# Ports.net
KiCad netlist of a schematic drawn in Altium Designer
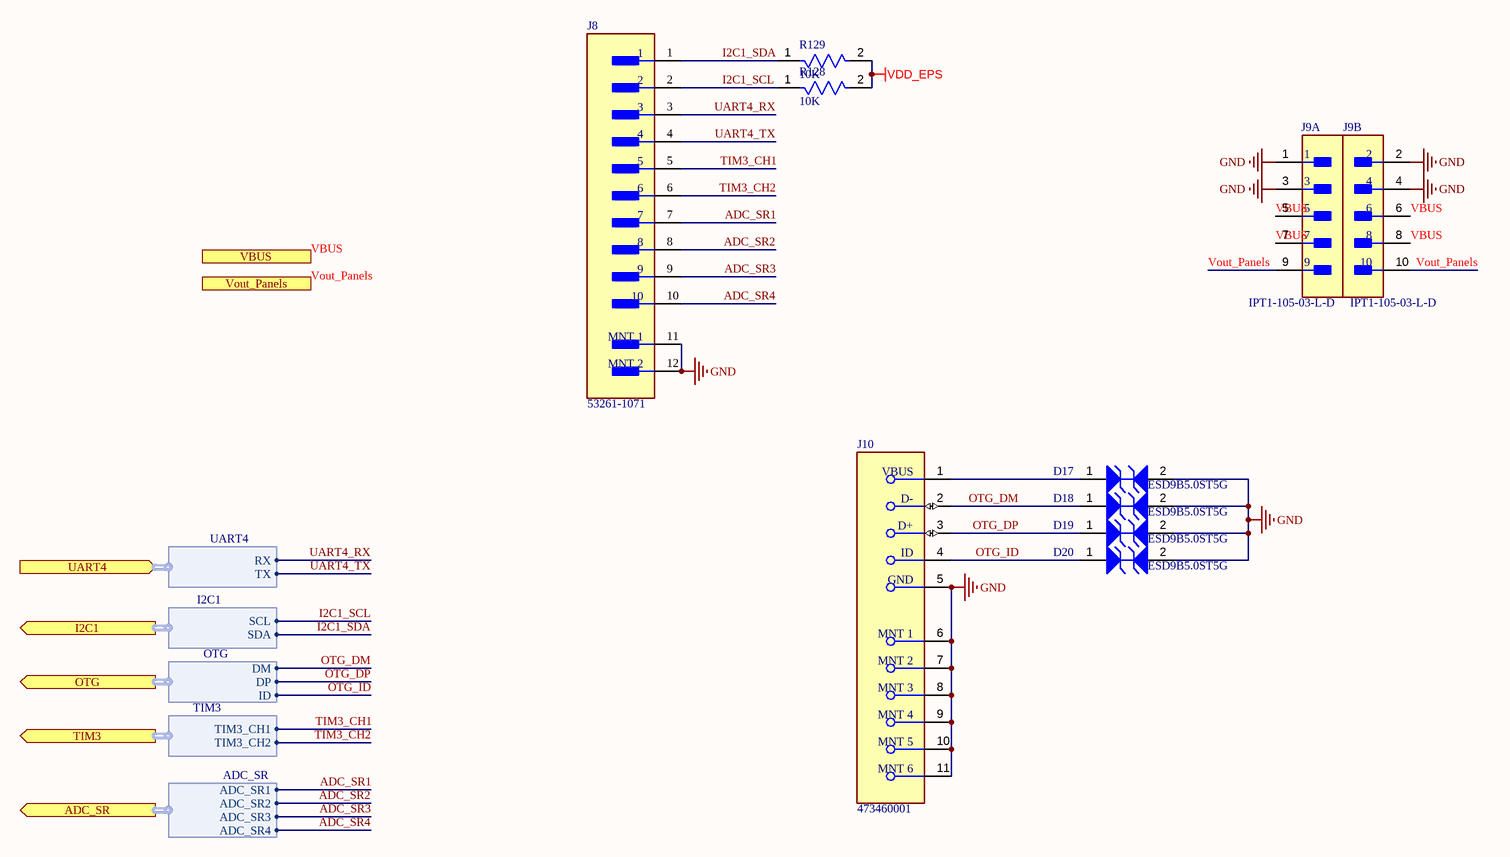
[diagram p0: Ports.SchDoc]

(export (version "E")
  (design (tool "Eeschema 10.0.6"))
  (components
    (comp (ref "D17")
      (value "ESD9B5.0ST5G")
      (footprint "ONSC-SOD-923-2-514AB-01_V")
      (fields (field (name "MANUFACTURER") "On Semiconductor"))
      (libsource (lib "Altium Content Vault") (part "ONSC-A1A2-2"))
    )
    (comp (ref "D18")
      (value "ESD9B5.0ST5G")
      (footprint "ONSC-SOD-923-2-514AB-01_V")
      (fields (field (name "MANUFACTURER") "On Semiconductor"))
      (libsource (lib "Altium Content Vault") (part "ONSC-A1A2-2"))
    )
    (comp (ref "D19")
      (value "ESD9B5.0ST5G")
      (footprint "ONSC-SOD-923-2-514AB-01_V")
      (fields (field (name "MANUFACTURER") "On Semiconductor"))
      (libsource (lib "Altium Content Vault") (part "ONSC-A1A2-2"))
    )
    (comp (ref "D20")
      (value "ESD9B5.0ST5G")
      (footprint "ONSC-SOD-923-2-514AB-01_V")
      (fields (field (name "MANUFACTURER") "On Semiconductor"))
      (libsource (lib "Altium Content Vault") (part "ONSC-A1A2-2"))
    )
    (comp (ref "J8")
      (value "53261-1071")
      (footprint "FP-532611071-MFG")
      (libsource (lib "Altium Content Vault") (part "6fa52caac0d1ee56d9e6a1d806c5b84"))
    )
    (comp (ref "J9")
      (value "IPT1-105-03-L-D")
      (footprint "FP-IPT1-105-03-L-D-MFG")
      (description "CONN HEADER VERT 10POS 2.54MM")
      (fields
        (field (name "MANUFACTURER") "Samtec")
        (field (name "OCTOPART") "https://octopart.com/ipt1-105-03-l-d-samtec-19544968")
      )
      (libsource (lib "") (part "544f42128f4185dcb88ce1ce9bf1982_1"))
    )
    (comp (ref "J10")
      (value "473460001")
      (footprint "FP-473460001-MFG")
      (description "CONN RCPT USB2.0 MICRO B SMD R/A")
      (fields
        (field (name "OCTOPART") "https://octopart.com/47346-0001-molex-7164928")
        (field (name "MANUFACTURER") "Molex")
      )
      (libsource (lib "Altium Content Vault") (part "53ae1f1d9b557310b43ca686e5bb76a"))
    )
    (comp (ref "R128")
      (value "10K")
      (footprint "FP-RK73B1J-MFG")
      (description "RES 10K OHM 5% 1/10W 0603")
      (fields (field (name "TOLERANCE") "5%"))
      (libsource (lib "Altium Content Vault") (part "1029c3af85768c4190bb7ad29bc67b5"))
    )
    (comp (ref "R129")
      (value "10K")
      (footprint "FP-RK73B1J-MFG")
      (description "RES 10K OHM 5% 1/10W 0603")
      (fields (field (name "TOLERANCE") "5%"))
      (libsource (lib "Altium Content Vault") (part "1029c3af85768c4190bb7ad29bc67b5"))
    )
  )
  (nets
    (net (code "6") (name "/ADC_SR1") (class "Default")
      (node (ref "J8") (pin "7") (pinfunction "7_7") (pintype "passive"))
    )
    (net (code "7") (name "/ADC_SR2") (class "Default")
      (node (ref "J8") (pin "8") (pinfunction "8_8") (pintype "passive"))
    )
    (net (code "8") (name "/ADC_SR3") (class "Default")
      (node (ref "J8") (pin "9") (pinfunction "9_9") (pintype "passive"))
    )
    (net (code "9") (name "/ADC_SR4") (class "Default")
      (node (ref "J8") (pin "10") (pinfunction "10_10") (pintype "passive"))
    )
    (net (code "10") (name "/I2C1_SCL") (class "Default")
      (node (ref "J8") (pin "2") (pinfunction "2_2") (pintype "passive"))
      (node (ref "R128") (pin "1") (pinfunction "1_1") (pintype "passive"))
    )
    (net (code "11") (name "/I2C1_SDA") (class "Default")
      (node (ref "J8") (pin "1") (pinfunction "1_1") (pintype "passive"))
      (node (ref "R129") (pin "1") (pinfunction "1_1") (pintype "passive"))
    )
    (net (code "12") (name "/OTG_DM") (class "Default")
      (node (ref "D18") (pin "1") (pinfunction "A1_1") (pintype "passive"))
      (node (ref "J10") (pin "2") (pinfunction "D-_2") (pintype "bidirectional"))
    )
    (net (code "13") (name "/OTG_DP") (class "Default")
      (node (ref "D19") (pin "1") (pinfunction "A1_1") (pintype "passive"))
      (node (ref "J10") (pin "3") (pinfunction "D+_3") (pintype "bidirectional"))
    )
    (net (code "14") (name "/OTG_ID") (class "Default")
      (node (ref "D20") (pin "1") (pinfunction "A1_1") (pintype "passive"))
      (node (ref "J10") (pin "4") (pinfunction "ID_4") (pintype "passive"))
    )
    (net (code "15") (name "/TIM3_CH1") (class "Default")
      (node (ref "J8") (pin "5") (pinfunction "5_5") (pintype "passive"))
    )
    (net (code "16") (name "/TIM3_CH2") (class "Default")
      (node (ref "J8") (pin "6") (pinfunction "6_6") (pintype "passive"))
    )
    (net (code "17") (name "/UART4_RX") (class "Default")
      (node (ref "J8") (pin "3") (pinfunction "3_3") (pintype "passive"))
    )
    (net (code "18") (name "/UART4_TX") (class "Default")
      (node (ref "J8") (pin "4") (pinfunction "4_4") (pintype "passive"))
    )
    (net (code "19") (name "/VBUS") (class "Default")
      (node (ref "J9") (pin "5") (pinfunction "5_5") (pintype "passive"))
      (node (ref "J9") (pin "6") (pinfunction "6_6") (pintype "passive"))
      (node (ref "J9") (pin "7") (pinfunction "7_7") (pintype "passive"))
      (node (ref "J9") (pin "8") (pinfunction "8_8") (pintype "passive"))
    )
    (net (code "20") (name "/Vout_Panels") (class "Default")
      (node (ref "J9") (pin "10") (pinfunction "10_10") (pintype "passive"))
      (node (ref "J9") (pin "9") (pinfunction "9_9") (pintype "passive"))
    )
    (net (code "26") (name "GND") (class "Default")
      (node (ref "D17") (pin "2") (pinfunction "A2_2") (pintype "passive"))
      (node (ref "D18") (pin "2") (pinfunction "A2_2") (pintype "passive"))
      (node (ref "D19") (pin "2") (pinfunction "A2_2") (pintype "passive"))
      (node (ref "D20") (pin "2") (pinfunction "A2_2") (pintype "passive"))
      (node (ref "J10") (pin "10") (pinfunction "MNT_5_10") (pintype "passive"))
      (node (ref "J10") (pin "11") (pinfunction "MNT_6_11") (pintype "passive"))
      (node (ref "J10") (pin "5") (pinfunction "GND_5") (pintype "power_in"))
      (node (ref "J10") (pin "6") (pinfunction "MNT_1_6") (pintype "passive"))
      (node (ref "J10") (pin "7") (pinfunction "MNT_2_7") (pintype "passive"))
      (node (ref "J10") (pin "8") (pinfunction "MNT_3_8") (pintype "passive"))
      (node (ref "J10") (pin "9") (pinfunction "MNT_4_9") (pintype "passive"))
      (node (ref "J8") (pin "11") (pinfunction "MNT_1_11") (pintype "passive"))
      (node (ref "J8") (pin "12") (pinfunction "MNT_2_12") (pintype "passive"))
      (node (ref "J9") (pin "1") (pinfunction "1_1") (pintype "passive"))
      (node (ref "J9") (pin "2") (pinfunction "2_2") (pintype "passive"))
      (node (ref "J9") (pin "3") (pinfunction "3_3") (pintype "passive"))
      (node (ref "J9") (pin "4") (pinfunction "4_4") (pintype "passive"))
    )
    (net (code "27") (name "Net-(D17-A1)") (class "Default")
      (node (ref "D17") (pin "1") (pinfunction "A1_1") (pintype "passive"))
      (node (ref "J10") (pin "1") (pinfunction "VBUS_1") (pintype "power_in"))
    )
    (net (code "28") (name "VDD_EPS") (class "Default")
      (node (ref "R128") (pin "2") (pinfunction "2_2") (pintype "passive"))
      (node (ref "R129") (pin "2") (pinfunction "2_2") (pintype "passive"))
    )
  )
)
